# PSU.net
KiCad netlist of a schematic drawn in Altium Designer
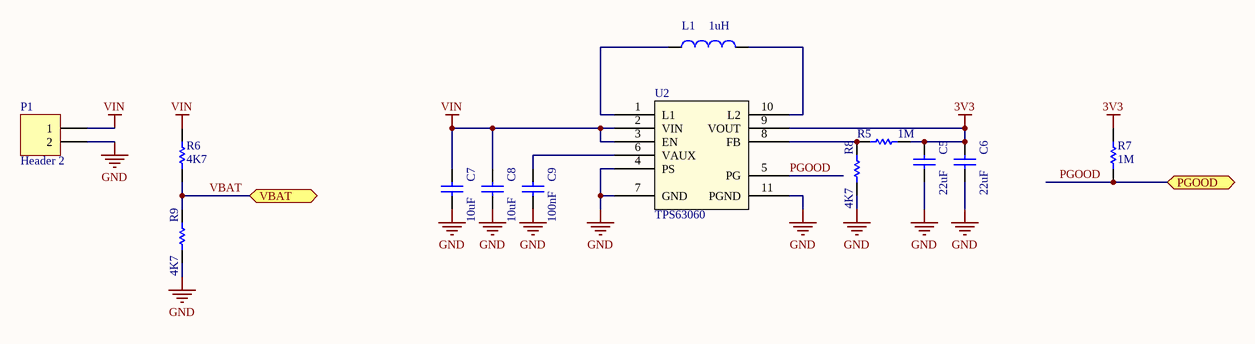
[diagram p0: PSU.SchDoc]

(export (version "E")
  (design (tool "Eeschema 10.0.6"))
  (components
    (comp (ref "C5")
      (value "22uF")
      (footprint "CAPC2512L")
      (description "Capacitor (Semiconductor SIM Model)")
      (fields (field (name "Comment") "CAP0603-") (field (name "PUBLISHER") "Altium Limited"))
      (libsource (lib "Miscellaneous Devices") (part "Cap Semi"))
    )
    (comp (ref "C6")
      (value "22uF")
      (footprint "CAPC2512L")
      (description "Capacitor (Semiconductor SIM Model)")
      (fields (field (name "Comment") "CAP0603-") (field (name "PUBLISHER") "Altium Limited"))
      (libsource (lib "Miscellaneous Devices") (part "Cap Semi"))
    )
    (comp (ref "C7")
      (value "10uF")
      (footprint "CAPC2512L")
      (description "Capacitor (Semiconductor SIM Model)")
      (fields (field (name "Comment") "CAP0603-") (field (name "PUBLISHER") "Altium Limited"))
      (libsource (lib "Miscellaneous Devices") (part "Cap Semi"))
    )
    (comp (ref "C8")
      (value "10uF")
      (footprint "CAPC2512L")
      (description "Capacitor (Semiconductor SIM Model)")
      (fields (field (name "Comment") "CAP0603-") (field (name "PUBLISHER") "Altium Limited"))
      (libsource (lib "Miscellaneous Devices") (part "Cap Semi"))
    )
    (comp (ref "C9")
      (value "100nF")
      (footprint "RESC2012L")
      (description "Capacitor (Semiconductor SIM Model)")
      (fields (field (name "Comment") "CAP0603-") (field (name "PUBLISHER") "Altium Limited"))
      (libsource (lib "Miscellaneous Devices") (part "Cap Semi"))
    )
    (comp (ref "L1")
      (value "1uH")
      (footprint "INDC3225M")
      (description "Inductor")
      (fields (field (name "Comment") "?") (field (name "PUBLISHER") "Altium Limited"))
      (libsource (lib "Miscellaneous Devices") (part "Inductor"))
    )
    (comp (ref "P1")
      (value "Header 2")
      (footprint "HDR1X2")
      (description "Header, 2-Pin")
      (fields (field (name "PUBLISHER") "Altium Limited"))
      (libsource (lib "Miscellaneous Connectors") (part "Header 2"))
    )
    (comp (ref "R5")
      (value "1M")
      (footprint "RESC2012L")
      (description "Semiconductor Resistor")
      (fields (field (name "Comment") "RES0603-") (field (name "PUBLISHER") "Altium Limited"))
      (libsource (lib "Miscellaneous Devices") (part "Res Semi"))
    )
    (comp (ref "R6")
      (value "4K7")
      (footprint "RESC2012L")
      (description "Semiconductor Resistor")
      (fields (field (name "Comment") "RES0603-") (field (name "PUBLISHER") "Altium Limited"))
      (libsource (lib "Miscellaneous Devices") (part "Res Semi"))
    )
    (comp (ref "R7")
      (value "1M")
      (footprint "RESC2012L")
      (description "Semiconductor Resistor")
      (fields (field (name "Comment") "RES0603-") (field (name "PUBLISHER") "Altium Limited"))
      (libsource (lib "Miscellaneous Devices") (part "Res Semi"))
    )
    (comp (ref "R8")
      (value "4K7")
      (footprint "RESC2012L")
      (description "Semiconductor Resistor")
      (fields (field (name "Comment") "RES0603-") (field (name "PUBLISHER") "Altium Limited"))
      (libsource (lib "Miscellaneous Devices") (part "Res Semi"))
    )
    (comp (ref "R9")
      (value "4K7")
      (footprint "RESC2012L")
      (description "Semiconductor Resistor")
      (fields (field (name "Comment") "RES0603-") (field (name "PUBLISHER") "Altium Limited"))
      (libsource (lib "Miscellaneous Devices") (part "Res Semi"))
    )
    (comp (ref "U2")
      (value "TPS63060")
      (footprint "SON50P300X300X100-11V")
      (description "Buck-Boost Regulator")
      (libsource (lib "ZigTemp") (part "TPS63060"))
    )
  )
  (nets
    (net (code "1") (name "/PGOOD") (class "Default")
      (node (ref "R7") (pin "2") (pinfunction "2_2") (pintype "passive"))
      (node (ref "U2") (pin "5") (pinfunction "PG_5") (pintype "passive"))
    )
    (net (code "2") (name "/VBAT") (class "Default")
      (node (ref "R6") (pin "2") (pinfunction "2_2") (pintype "passive"))
      (node (ref "R9") (pin "2") (pinfunction "2_2") (pintype "passive"))
    )
    (net (code "3") (name "3V3") (class "Default")
      (node (ref "C5") (pin "2") (pinfunction "2_2") (pintype "passive"))
      (node (ref "C6") (pin "2") (pinfunction "2_2") (pintype "passive"))
      (node (ref "R5") (pin "1") (pinfunction "1_1") (pintype "passive"))
      (node (ref "R7") (pin "1") (pinfunction "1_1") (pintype "passive"))
      (node (ref "U2") (pin "9") (pinfunction "VOUT_9") (pintype "passive"))
    )
    (net (code "4") (name "GND") (class "Default")
      (node (ref "C5") (pin "1") (pinfunction "1_1") (pintype "passive"))
      (node (ref "C6") (pin "1") (pinfunction "1_1") (pintype "passive"))
      (node (ref "C7") (pin "1") (pinfunction "1_1") (pintype "passive"))
      (node (ref "C8") (pin "1") (pinfunction "1_1") (pintype "passive"))
      (node (ref "C9") (pin "1") (pinfunction "1_1") (pintype "passive"))
      (node (ref "P1") (pin "2") (pinfunction "2_2") (pintype "passive"))
      (node (ref "R8") (pin "1") (pinfunction "1_1") (pintype "passive"))
      (node (ref "R9") (pin "1") (pinfunction "1_1") (pintype "passive"))
      (node (ref "U2") (pin "11") (pinfunction "PGND_11") (pintype "passive"))
      (node (ref "U2") (pin "4") (pinfunction "PS_4") (pintype "passive"))
      (node (ref "U2") (pin "7") (pinfunction "GND_7") (pintype "passive"))
    )
    (net (code "5") (name "Net-(U2-FB)") (class "Default")
      (node (ref "R5") (pin "2") (pinfunction "2_2") (pintype "passive"))
      (node (ref "R8") (pin "2") (pinfunction "2_2") (pintype "passive"))
      (node (ref "U2") (pin "8") (pinfunction "FB_8") (pintype "passive"))
    )
    (net (code "6") (name "Net-(U2-L1)") (class "Default")
      (node (ref "L1") (pin "1") (pinfunction "1_1") (pintype "passive"))
      (node (ref "U2") (pin "1") (pinfunction "L1_1") (pintype "passive"))
    )
    (net (code "7") (name "Net-(U2-L2)") (class "Default")
      (node (ref "L1") (pin "2") (pinfunction "2_2") (pintype "passive"))
      (node (ref "U2") (pin "10") (pinfunction "L2_10") (pintype "passive"))
    )
    (net (code "8") (name "Net-(U2-VAUX)") (class "Default")
      (node (ref "C9") (pin "2") (pinfunction "2_2") (pintype "passive"))
      (node (ref "U2") (pin "6") (pinfunction "VAUX_6") (pintype "passive"))
    )
    (net (code "9") (name "VIN") (class "Default")
      (node (ref "C7") (pin "2") (pinfunction "2_2") (pintype "passive"))
      (node (ref "C8") (pin "2") (pinfunction "2_2") (pintype "passive"))
      (node (ref "P1") (pin "1") (pinfunction "1_1") (pintype "passive"))
      (node (ref "R6") (pin "1") (pinfunction "1_1") (pintype "passive"))
      (node (ref "U2") (pin "2") (pinfunction "VIN_2") (pintype "passive"))
      (node (ref "U2") (pin "3") (pinfunction "EN_3") (pintype "passive"))
    )
  )
)
